# FuenteDePoder.net
KiCad netlist of a schematic drawn in EAGLE
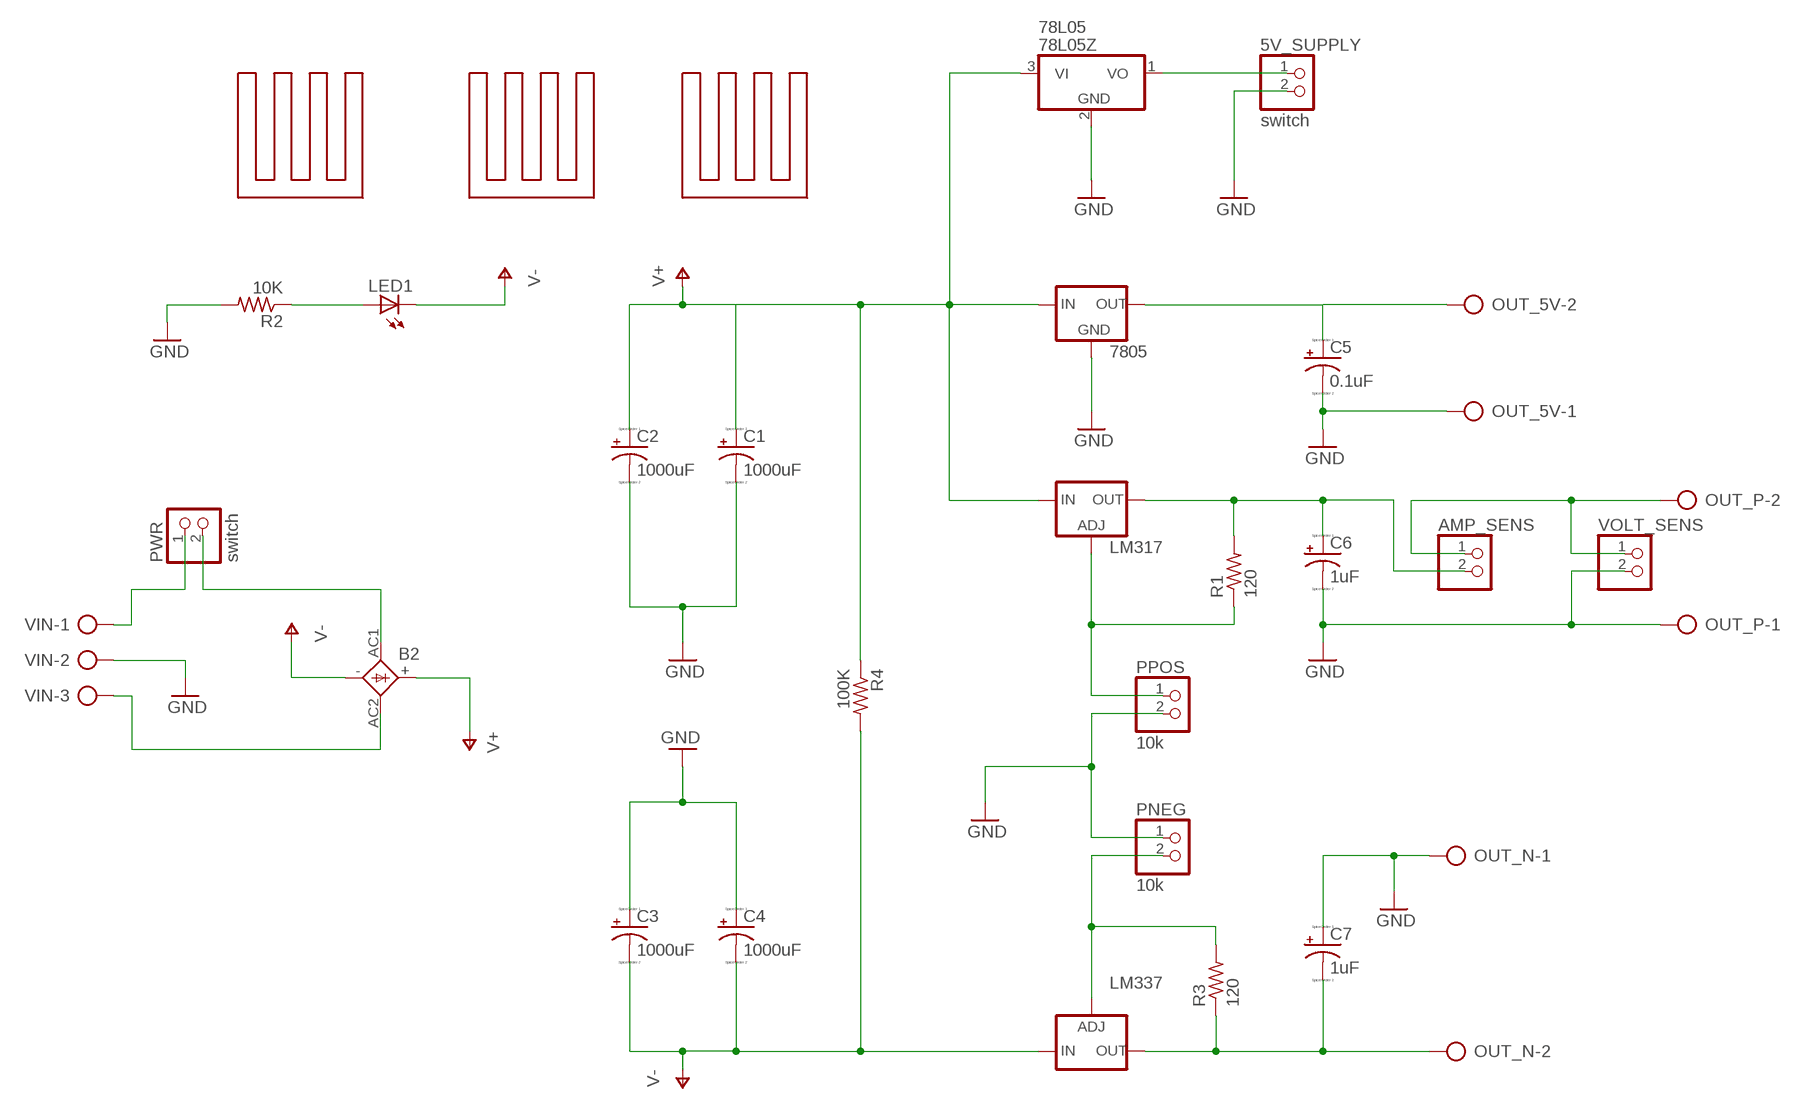
[diagram p0: schematic, sheet 1]

(export (version "E")
  (design (tool "Eeschema 10.0.6"))
  (components
    (comp (ref "5V_SUPPLY")
      (value "switch")
      (footprint "eagle-import:1X02")
      (libsource (lib "eagle-import") (part "PINHD-1X2"))
    )
    (comp (ref "78L05")
      (value "78L05Z")
      (footprint "eagle-import:TO92")
      (libsource (lib "eagle-import") (part "78ZL05"))
    )
    (comp (ref "7805")
      (value "78XXS")
      (footprint "eagle-import:78XXS")
      (libsource (lib "eagle-import") (part "78XXS"))
    )
    (comp (ref "AMP_SENS")
      (value "PINHD-1X2")
      (footprint "eagle-import:1X02")
      (libsource (lib "eagle-import") (part "PINHD-1X2"))
    )
    (comp (ref "B2")
      (value "GBPC6")
      (footprint "eagle-import:GBPC6")
      (libsource (lib "eagle-import") (part "GBPC6"))
    )
    (comp (ref "C1")
      (value "1000uF")
      (footprint "eagle-import:E3,5-10")
      (libsource (lib "eagle-import") (part "CPOL-USE3.5-10"))
    )
    (comp (ref "C2")
      (value "1000uF")
      (footprint "eagle-import:E3,5-10")
      (libsource (lib "eagle-import") (part "CPOL-USE3.5-10"))
    )
    (comp (ref "C3")
      (value "1000uF")
      (footprint "eagle-import:E3,5-10")
      (libsource (lib "eagle-import") (part "CPOL-USE3.5-10"))
    )
    (comp (ref "C4")
      (value "1000uF")
      (footprint "eagle-import:E3,5-10")
      (libsource (lib "eagle-import") (part "CPOL-USE3.5-10"))
    )
    (comp (ref "C5")
      (value "0.1uF")
      (footprint "eagle-import:E1,8-4")
      (libsource (lib "eagle-import") (part "CPOL-USE1.8-4"))
    )
    (comp (ref "C6")
      (value "1uF")
      (footprint "eagle-import:E1,8-4")
      (libsource (lib "eagle-import") (part "CPOL-USE1.8-4"))
    )
    (comp (ref "C7")
      (value "1uF")
      (footprint "eagle-import:E1,8-4")
      (libsource (lib "eagle-import") (part "CPOL-USE1.8-4"))
    )
    (comp (ref "LED1")
      (value "LED5MM")
      (footprint "eagle-import:LED5MM")
      (libsource (lib "eagle-import") (part "LED5MM"))
    )
    (comp (ref "LM317")
      (value "LM317TS")
      (footprint "eagle-import:317TS")
      (libsource (lib "eagle-import") (part "LM317TS"))
    )
    (comp (ref "LM337")
      (value "LM337TS")
      (footprint "eagle-import:337TS")
      (libsource (lib "eagle-import") (part "LM337TS"))
    )
    (comp (ref "OUT_5V")
      (value "AK300/2")
      (footprint "eagle-import:AK300_2")
      (libsource (lib "eagle-import") (part "AK300/2"))
    )
    (comp (ref "OUT_N")
      (value "AK300/2")
      (footprint "eagle-import:AK300_2")
      (libsource (lib "eagle-import") (part "AK300/2"))
    )
    (comp (ref "OUT_P")
      (value "AK300/2")
      (footprint "eagle-import:AK300_2")
      (libsource (lib "eagle-import") (part "AK300/2"))
    )
    (comp (ref "PNEG")
      (value "10k")
      (footprint "eagle-import:1X02")
      (libsource (lib "eagle-import") (part "PINHD-1X2"))
    )
    (comp (ref "PPOS")
      (value "10k")
      (footprint "eagle-import:1X02")
      (libsource (lib "eagle-import") (part "PINHD-1X2"))
    )
    (comp (ref "PWR")
      (value "switch")
      (footprint "eagle-import:1X02")
      (libsource (lib "eagle-import") (part "PINHD-1X2"))
    )
    (comp (ref "R1")
      (value "120")
      (footprint "eagle-import:0204_7")
      (libsource (lib "eagle-import") (part "R-US_0204/7"))
    )
    (comp (ref "R2")
      (value "10K")
      (footprint "eagle-import:0204_7")
      (libsource (lib "eagle-import") (part "R-US_0204/7"))
    )
    (comp (ref "R3")
      (value "120")
      (footprint "eagle-import:0204_7")
      (libsource (lib "eagle-import") (part "R-US_0204/7"))
    )
    (comp (ref "R4")
      (value "100K")
      (footprint "eagle-import:0204_7")
      (libsource (lib "eagle-import") (part "R-US_0204/7"))
    )
    (comp (ref "U$1")
      (value "HEATSINK")
      (footprint "eagle-import:HEATSINK")
      (libsource (lib "eagle-import") (part "HEATSINK"))
    )
    (comp (ref "U$2")
      (value "HEATSINK")
      (footprint "eagle-import:HEATSINK")
      (libsource (lib "eagle-import") (part "HEATSINK"))
    )
    (comp (ref "U$3")
      (value "HEATSINK")
      (footprint "eagle-import:HEATSINK")
      (libsource (lib "eagle-import") (part "HEATSINK"))
    )
    (comp (ref "VIN")
      (value "AK300/3")
      (footprint "eagle-import:AK300_3")
      (libsource (lib "eagle-import") (part "AK300/3"))
    )
    (comp (ref "VOLT_SENS")
      (value "PINHD-1X2")
      (footprint "eagle-import:1X02")
      (libsource (lib "eagle-import") (part "PINHD-1X2"))
    )
  )
  (nets
    (net (code "1") (name "GND") (class "Default")
      (node (ref "5V_SUPPLY") (pin "2") (pinfunction "2_2") (pintype "passive"))
      (node (ref "7805") (pin "GND") (pinfunction "GND_GND") (pintype "input"))
      (node (ref "78L05") (pin "2") (pinfunction "GND_2") (pintype "passive"))
      (node (ref "C1") (pin "-") (pinfunction "-_-") (pintype "passive"))
      (node (ref "C2") (pin "-") (pinfunction "-_-") (pintype "passive"))
      (node (ref "C3") (pin "+") (pinfunction "+_+") (pintype "passive"))
      (node (ref "C4") (pin "+") (pinfunction "+_+") (pintype "passive"))
      (node (ref "C5") (pin "-") (pinfunction "-_-") (pintype "passive"))
      (node (ref "C6") (pin "-") (pinfunction "-_-") (pintype "passive"))
      (node (ref "C7") (pin "+") (pinfunction "+_+") (pintype "passive"))
      (node (ref "OUT_5V") (pin "1") (pinfunction "KL_1") (pintype "passive"))
      (node (ref "OUT_N") (pin "1") (pinfunction "KL_1") (pintype "passive"))
      (node (ref "OUT_P") (pin "1") (pinfunction "KL_1") (pintype "passive"))
      (node (ref "PNEG") (pin "1") (pinfunction "1_1") (pintype "passive"))
      (node (ref "PPOS") (pin "2") (pinfunction "2_2") (pintype "passive"))
      (node (ref "R2") (pin "2") (pinfunction "2_2") (pintype "passive"))
      (node (ref "VIN") (pin "2") (pinfunction "KL_2") (pintype "passive"))
      (node (ref "VOLT_SENS") (pin "2") (pinfunction "2_2") (pintype "passive"))
    )
    (net (code "2") (name "Net-(78L05-VO)") (class "Default")
      (node (ref "5V_SUPPLY") (pin "1") (pinfunction "1_1") (pintype "passive"))
      (node (ref "78L05") (pin "1") (pinfunction "VO_1") (pintype "passive"))
    )
    (net (code "3") (name "Net-(B2-PadAC1)") (class "Default")
      (node (ref "B2") (pin "AC1") (pinfunction "AC1_AC1") (pintype "passive"))
      (node (ref "PWR") (pin "2") (pinfunction "2_2") (pintype "passive"))
    )
    (net (code "4") (name "Net-(LED1-PadA)") (class "Default")
      (node (ref "LED1") (pin "A") (pinfunction "A_A") (pintype "passive"))
      (node (ref "R2") (pin "1") (pinfunction "1_1") (pintype "passive"))
    )
    (net (code "5") (name "Net-(LM317-ADJ)") (class "Default")
      (node (ref "LM317") (pin "1") (pinfunction "ADJ_1") (pintype "input"))
      (node (ref "PPOS") (pin "1") (pinfunction "1_1") (pintype "passive"))
      (node (ref "R1") (pin "1") (pinfunction "1_1") (pintype "passive"))
    )
    (net (code "6") (name "Net-(LM317-OUT)") (class "Default")
      (node (ref "AMP_SENS") (pin "2") (pinfunction "2_2") (pintype "passive"))
      (node (ref "C6") (pin "+") (pinfunction "+_+") (pintype "passive"))
      (node (ref "LM317") (pin "2") (pinfunction "OUT_2") (pintype "passive"))
      (node (ref "R1") (pin "2") (pinfunction "2_2") (pintype "passive"))
    )
    (net (code "7") (name "Net-(LM337-ADJ)") (class "Default")
      (node (ref "LM337") (pin "1") (pinfunction "ADJ_1") (pintype "input"))
      (node (ref "PNEG") (pin "2") (pinfunction "2_2") (pintype "passive"))
      (node (ref "R3") (pin "2") (pinfunction "2_2") (pintype "passive"))
    )
    (net (code "8") (name "Net-(LM337-OUT)") (class "Default")
      (node (ref "C7") (pin "-") (pinfunction "-_-") (pintype "passive"))
      (node (ref "LM337") (pin "3") (pinfunction "OUT_3") (pintype "passive"))
      (node (ref "OUT_N") (pin "2") (pinfunction "KL_2") (pintype "passive"))
      (node (ref "R3") (pin "1") (pinfunction "1_1") (pintype "passive"))
    )
    (net (code "9") (name "Net-(OUT_5VB-KL)") (class "Default")
      (node (ref "7805") (pin "OUT") (pinfunction "OUT_OUT") (pintype "passive"))
      (node (ref "C5") (pin "+") (pinfunction "+_+") (pintype "passive"))
      (node (ref "OUT_5V") (pin "2") (pinfunction "KL_2") (pintype "passive"))
    )
    (net (code "10") (name "Net-(OUT_PB-KL)") (class "Default")
      (node (ref "AMP_SENS") (pin "1") (pinfunction "1_1") (pintype "passive"))
      (node (ref "OUT_P") (pin "2") (pinfunction "KL_2") (pintype "passive"))
      (node (ref "VOLT_SENS") (pin "1") (pinfunction "1_1") (pintype "passive"))
    )
    (net (code "11") (name "Net-(VINA-KL)") (class "Default")
      (node (ref "PWR") (pin "1") (pinfunction "1_1") (pintype "passive"))
      (node (ref "VIN") (pin "1") (pinfunction "KL_1") (pintype "passive"))
    )
    (net (code "12") (name "Net-(VINC-KL)") (class "Default")
      (node (ref "B2") (pin "AC2") (pinfunction "AC2_AC2") (pintype "passive"))
      (node (ref "VIN") (pin "3") (pinfunction "KL_3") (pintype "passive"))
    )
    (net (code "13") (name "V+") (class "Default")
      (node (ref "7805") (pin "IN") (pinfunction "IN_IN") (pintype "input"))
      (node (ref "78L05") (pin "3") (pinfunction "VI_3") (pintype "input"))
      (node (ref "B2") (pin "+") (pinfunction "+_+") (pintype "passive"))
      (node (ref "C1") (pin "+") (pinfunction "+_+") (pintype "passive"))
      (node (ref "C2") (pin "+") (pinfunction "+_+") (pintype "passive"))
      (node (ref "LM317") (pin "3") (pinfunction "IN_3") (pintype "input"))
      (node (ref "R4") (pin "1") (pinfunction "1_1") (pintype "passive"))
    )
    (net (code "14") (name "V-") (class "Default")
      (node (ref "B2") (pin "-") (pinfunction "-_-") (pintype "passive"))
      (node (ref "C3") (pin "-") (pinfunction "-_-") (pintype "passive"))
      (node (ref "C4") (pin "-") (pinfunction "-_-") (pintype "passive"))
      (node (ref "LED1") (pin "K") (pinfunction "C_K") (pintype "passive"))
      (node (ref "LM337") (pin "2") (pinfunction "IN_2") (pintype "input"))
      (node (ref "R4") (pin "2") (pinfunction "2_2") (pintype "passive"))
    )
  )
)
